# tiny13_charlie4_50mm_AAA_optical_diag.net
KiCad netlist of a schematic drawn in EAGLE
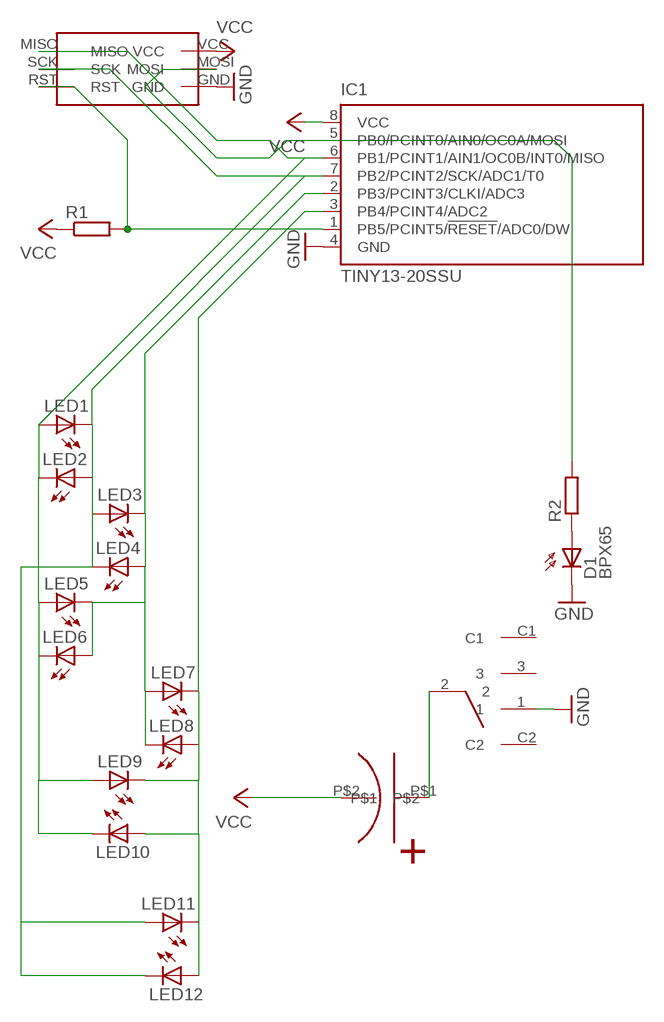
[diagram p0: schematic, sheet 1]

(export (version "E")
  (design (tool "Eeschema 10.0.6"))
  (components
    (comp (ref "D1")
      (value "BPX65")
      (footprint "eagle-import:BPX65")
      (fields (field (name "MPN") "BPX65."))
      (libsource (lib "eagle-import") (part "BPX65"))
    )
    (comp (ref "IC1")
      (value "TINY13-20SSU")
      (footprint "eagle-import:8S1")
      (fields (field (name "MPN") "ATTINY13-20SSU"))
      (libsource (lib "eagle-import") (part "TINY13SSU-20"))
    )
    (comp (ref "LED1")
      (value "LED3MM")
      (footprint "eagle-import:LED3MM")
      (libsource (lib "eagle-import") (part "LED3MM"))
    )
    (comp (ref "LED2")
      (value "LED3MM")
      (footprint "eagle-import:LED3MM")
      (libsource (lib "eagle-import") (part "LED3MM"))
    )
    (comp (ref "LED3")
      (value "LED3MM")
      (footprint "eagle-import:LED3MM")
      (libsource (lib "eagle-import") (part "LED3MM"))
    )
    (comp (ref "LED4")
      (value "LED3MM")
      (footprint "eagle-import:LED3MM")
      (libsource (lib "eagle-import") (part "LED3MM"))
    )
    (comp (ref "LED5")
      (value "LED3MM")
      (footprint "eagle-import:LED3MM")
      (libsource (lib "eagle-import") (part "LED3MM"))
    )
    (comp (ref "LED6")
      (value "LED3MM")
      (footprint "eagle-import:LED3MM")
      (libsource (lib "eagle-import") (part "LED3MM"))
    )
    (comp (ref "LED7")
      (value "LED3MM")
      (footprint "eagle-import:LED3MM")
      (libsource (lib "eagle-import") (part "LED3MM"))
    )
    (comp (ref "LED8")
      (value "LED3MM")
      (footprint "eagle-import:LED3MM")
      (libsource (lib "eagle-import") (part "LED3MM"))
    )
    (comp (ref "LED9")
      (value "LED3MM")
      (footprint "eagle-import:LED3MM")
      (libsource (lib "eagle-import") (part "LED3MM"))
    )
    (comp (ref "LED10")
      (value "LED3MM")
      (footprint "eagle-import:LED3MM")
      (libsource (lib "eagle-import") (part "LED3MM"))
    )
    (comp (ref "LED11")
      (value "LED3MM")
      (footprint "eagle-import:LED3MM")
      (libsource (lib "eagle-import") (part "LED3MM"))
    )
    (comp (ref "LED12")
      (value "LED3MM")
      (footprint "eagle-import:LED3MM")
      (libsource (lib "eagle-import") (part "LED3MM"))
    )
    (comp (ref "R1")
      (value "R-EU_0204/5")
      (footprint "eagle-import:0204_5")
      (libsource (lib "eagle-import") (part "R-EU_0204/5"))
    )
    (comp (ref "R2")
      (value "R-EU_0204/5")
      (footprint "eagle-import:0204_5")
      (libsource (lib "eagle-import") (part "R-EU_0204/5"))
    )
    (comp (ref "U$2")
      (value "AVR_ISP_6_PIN_1X6_SMT_CONTACT_BIG")
      (footprint "eagle-import:CONTACT_ISP_PROGRAMMER_1X6_ATMEL")
      (libsource (lib "eagle-import") (part "AVR_ISP_6_PIN_1X6_SMT_CONTACT_BIG"))
    )
    (comp (ref "U$4")
      (value "SWITCH")
      (footprint "eagle-import:SWITCH")
      (libsource (lib "eagle-import") (part "SWITCH"))
    )
    (comp (ref "U$5")
      (value "NICHICON_12F")
      (footprint "eagle-import:NICHICON_10X30")
      (libsource (lib "eagle-import") (part "NICHICON_12F"))
    )
  )
  (nets
    (net (code "1") (name "GND") (class "Default")
      (node (ref "D1") (pin "K") (pinfunction "C_K") (pintype "passive"))
      (node (ref "IC1") (pin "4") (pinfunction "GND_4") (pintype "power_in"))
      (node (ref "U$2") (pin "GND") (pinfunction "GND_GND") (pintype "bidirectional"))
      (node (ref "U$4") (pin "1") (pinfunction "1_1") (pintype "bidirectional"))
    )
    (net (code "2") (name "Net-(D1-PadA)") (class "Default")
      (node (ref "D1") (pin "A") (pinfunction "A_A") (pintype "passive"))
      (node (ref "R2") (pin "1") (pinfunction "1_1") (pintype "passive"))
    )
    (net (code "3") (name "Net-(IC1-PB0{slash}PCINT0{slash}AIN0{slash}OC0A{slash}MOSI)") (class "Default")
      (node (ref "IC1") (pin "5") (pinfunction "PB0/PCINT0/AIN0/OC0A/MOSI_5") (pintype "bidirectional"))
      (node (ref "R2") (pin "2") (pinfunction "2_2") (pintype "passive"))
      (node (ref "U$2") (pin "MOSI") (pinfunction "MOSI_MOSI") (pintype "bidirectional"))
    )
    (net (code "4") (name "Net-(IC1-PB1{slash}PCINT1{slash}AIN1{slash}OC0B{slash}INT0{slash}MISO)") (class "Default")
      (node (ref "IC1") (pin "6") (pinfunction "PB1/PCINT1/AIN1/OC0B/INT0/MISO_6") (pintype "bidirectional"))
      (node (ref "LED1") (pin "A") (pinfunction "A_A") (pintype "passive"))
      (node (ref "LED10") (pin "K") (pinfunction "C_K") (pintype "passive"))
      (node (ref "LED2") (pin "K") (pinfunction "C_K") (pintype "passive"))
      (node (ref "LED5") (pin "A") (pinfunction "A_A") (pintype "passive"))
      (node (ref "LED6") (pin "K") (pinfunction "C_K") (pintype "passive"))
      (node (ref "LED9") (pin "A") (pinfunction "A_A") (pintype "passive"))
      (node (ref "U$2") (pin "MISO") (pinfunction "MISO_MISO") (pintype "bidirectional"))
    )
    (net (code "5") (name "Net-(IC1-PB2{slash}PCINT2{slash}SCK{slash}ADC1{slash}T0)") (class "Default")
      (node (ref "IC1") (pin "7") (pinfunction "PB2/PCINT2/SCK/ADC1/T0_7") (pintype "bidirectional"))
      (node (ref "LED1") (pin "K") (pinfunction "C_K") (pintype "passive"))
      (node (ref "LED11") (pin "A") (pinfunction "A_A") (pintype "passive"))
      (node (ref "LED12") (pin "K") (pinfunction "C_K") (pintype "passive"))
      (node (ref "LED2") (pin "A") (pinfunction "A_A") (pintype "passive"))
      (node (ref "LED3") (pin "A") (pinfunction "A_A") (pintype "passive"))
      (node (ref "LED4") (pin "K") (pinfunction "C_K") (pintype "passive"))
      (node (ref "U$2") (pin "SCK") (pinfunction "SCK_SCK") (pintype "bidirectional"))
    )
    (net (code "6") (name "Net-(IC1-PB3{slash}PCINT3{slash}CLKI{slash}ADC3)") (class "Default")
      (node (ref "IC1") (pin "2") (pinfunction "PB3/PCINT3/CLKI/ADC3_2") (pintype "bidirectional"))
      (node (ref "LED3") (pin "K") (pinfunction "C_K") (pintype "passive"))
      (node (ref "LED4") (pin "A") (pinfunction "A_A") (pintype "passive"))
      (node (ref "LED5") (pin "K") (pinfunction "C_K") (pintype "passive"))
      (node (ref "LED6") (pin "A") (pinfunction "A_A") (pintype "passive"))
      (node (ref "LED7") (pin "A") (pinfunction "A_A") (pintype "passive"))
      (node (ref "LED8") (pin "K") (pinfunction "C_K") (pintype "passive"))
    )
    (net (code "7") (name "Net-(IC1-PB4{slash}PCINT4{slash}ADC2)") (class "Default")
      (node (ref "IC1") (pin "3") (pinfunction "PB4/PCINT4/ADC2_3") (pintype "bidirectional"))
      (node (ref "LED10") (pin "A") (pinfunction "A_A") (pintype "passive"))
      (node (ref "LED11") (pin "K") (pinfunction "C_K") (pintype "passive"))
      (node (ref "LED12") (pin "A") (pinfunction "A_A") (pintype "passive"))
      (node (ref "LED7") (pin "K") (pinfunction "C_K") (pintype "passive"))
      (node (ref "LED8") (pin "A") (pinfunction "A_A") (pintype "passive"))
      (node (ref "LED9") (pin "K") (pinfunction "C_K") (pintype "passive"))
    )
    (net (code "8") (name "Net-(IC1-PB5{slash}PCINT5{slash}~{RESET}{slash}ADC0{slash}DW)") (class "Default")
      (node (ref "IC1") (pin "1") (pinfunction "PB5/PCINT5/~{RESET}/ADC0/DW_1") (pintype "bidirectional"))
      (node (ref "R1") (pin "2") (pinfunction "2_2") (pintype "passive"))
      (node (ref "U$2") (pin "RST") (pinfunction "RST_RST") (pintype "bidirectional"))
    )
    (net (code "9") (name "Net-(U$4-Pad2)") (class "Default")
      (node (ref "U$4") (pin "2") (pinfunction "2_2") (pintype "bidirectional"))
      (node (ref "U$5") (pin "P$1") (pinfunction "P$1_P$1") (pintype "bidirectional"))
    )
    (net (code "10") (name "VCC") (class "Default")
      (node (ref "IC1") (pin "8") (pinfunction "VCC_8") (pintype "power_in"))
      (node (ref "R1") (pin "1") (pinfunction "1_1") (pintype "passive"))
      (node (ref "U$2") (pin "VCC") (pinfunction "VCC_VCC") (pintype "bidirectional"))
      (node (ref "U$5") (pin "P$2") (pinfunction "P$2_P$2") (pintype "bidirectional"))
    )
    (net (code "11") (name "unconnected-(U$4-Pad3)") (class "Default")
      (node (ref "U$4") (pin "3") (pinfunction "3_3") (pintype "bidirectional"))
    )
    (net (code "12") (name "unconnected-(U$4-PadC1)") (class "Default")
      (node (ref "U$4") (pin "C1") (pinfunction "C1_C1") (pintype "bidirectional"))
    )
    (net (code "13") (name "unconnected-(U$4-PadC2)") (class "Default")
      (node (ref "U$4") (pin "C2") (pinfunction "C2_C2") (pintype "bidirectional"))
    )
  )
)
